# Power.net
KiCad netlist of a schematic drawn in Altium Designer
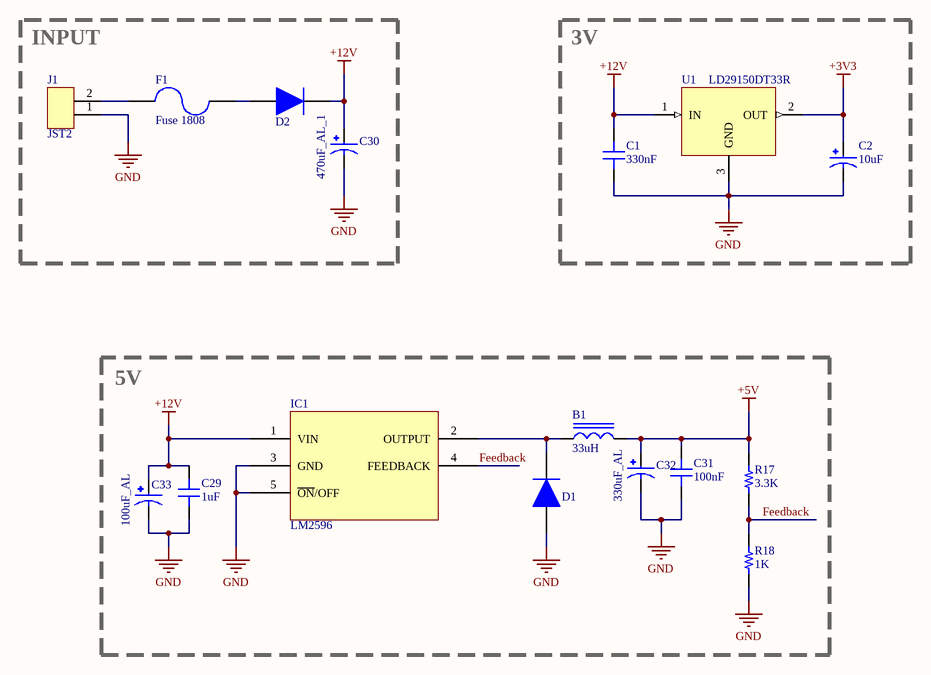
[diagram p0: Power.SchDoc]

(export (version "E")
  (design (tool "Eeschema 10.0.6"))
  (components
    (comp (ref "B1")
      (value "33uH")
      (footprint "DR125")
      (description "DR125")
      (libsource (lib "hava_kalitesi_olcumu") (part "33uH"))
    )
    (comp (ref "C1")
      (value "330nF")
      (footprint "CAP 0603_1608")
      (description "CERAMİC 1206 SMD")
      (libsource (lib "hava_kalitesi_olcumu") (part "330nF"))
    )
    (comp (ref "C2")
      (value "10uF")
      (footprint "TANTAL B-CASE")
      (description "TANTAL")
      (libsource (lib "hava_kalitesi_olcumu") (part "10uF"))
    )
    (comp (ref "C29")
      (value "1uF")
      (footprint "CAP 0603_1608")
      (description "CERAMİC 1206 SMD")
      (libsource (lib "hava_kalitesi_olcumu") (part "1uF"))
    )
    (comp (ref "C30")
      (value "470uF_AL_1")
      (footprint "10x12 Al Cap")
      (description "Aluminium Electrolytic Capacitors")
      (libsource (lib "hava_kalitesi_olcumu") (part "470uF_AL_1"))
    )
    (comp (ref "C31")
      (value "100nF")
      (footprint "CAP 0603_1608")
      (description "CERAMİC 1206 SMD")
      (libsource (lib "hava_kalitesi_olcumu") (part "100nF"))
    )
    (comp (ref "C32")
      (value "330uF_AL")
      (footprint "10x12 Al Cap")
      (description "Aluminium Electrolytic Capacitors")
      (libsource (lib "hava_kalitesi_olcumu") (part "330uF_AL"))
    )
    (comp (ref "C33")
      (value "100uF_AL")
      (footprint "10x12 Al Cap")
      (description "Aluminium Electrolytic Capacitors")
      (libsource (lib "hava_kalitesi_olcumu") (part "100uF_AL"))
    )
    (comp (ref "D1")
      (value "1N4148WS")
      (footprint "SOD323F")
      (description "Diode, Single, 75 V, 150 mA, 1 V, 4 ns")
      (fields (field (name "MANUFACTURER") "ON Semiconductor / Fairchild"))
      (libsource (lib "hava_kalitesi_olcumu") (part "1N4148WS"))
    )
    (comp (ref "D2")
      (value "1N4148WS")
      (footprint "SOD323F")
      (description "Diode, Single, 75 V, 150 mA, 1 V, 4 ns")
      (fields (field (name "MANUFACTURER") "ON Semiconductor / Fairchild"))
      (libsource (lib "hava_kalitesi_olcumu") (part "1N4148WS"))
    )
    (comp (ref "F1")
      (value "Fuse 1808")
      (footprint "1808")
      (description "FUSE BRD MNT 125VAC/VDC")
      (libsource (lib "hava_kalitesi_olcumu") (part "FUSE"))
    )
    (comp (ref "IC1")
      (value "LM2596")
      (footprint "D2PAK")
      (description "Buck Converter")
      (libsource (lib "hava_kalitesi_olcumu") (part "LM2596"))
    )
    (comp (ref "J1")
      (value "JST2")
      (footprint "JST2")
      (description "2 PIN 2.54MM")
      (libsource (lib "hava_kalitesi_olcumu") (part "JST2"))
    )
    (comp (ref "R17")
      (value "3.3K")
      (footprint "RES 0603_1608")
      (description "SMT RES 1206")
      (libsource (lib "hava_kalitesi_olcumu") (part "3.3K"))
    )
    (comp (ref "R18")
      (value "1K")
      (footprint "RES 0603_1608")
      (description "SMT RES 1206")
      (libsource (lib "hava_kalitesi_olcumu") (part "1K"))
    )
    (comp (ref "U1")
      (value "LD29150DT33R")
      (footprint "TO252-3 DPAK")
      (description "IC-29150 REG LDO 3V3 1.5A DPAK")
      (libsource (lib "hava_kalitesi_olcumu") (part "LD29150"))
    )
  )
  (nets
    (net (code "1") (name "+3V3") (class "Default")
      (node (ref "C2") (pin "+") (pinfunction "+_+") (pintype "passive"))
      (node (ref "U1") (pin "2") (pinfunction "OUT_2") (pintype "output"))
    )
    (net (code "2") (name "+5V") (class "Default")
      (node (ref "B1") (pin "2") (pinfunction "2_2") (pintype "passive"))
      (node (ref "C31") (pin "2") (pinfunction "2_2") (pintype "passive"))
      (node (ref "C32") (pin "1") (pinfunction "+_1") (pintype "passive"))
      (node (ref "R17") (pin "2") (pinfunction "2_2") (pintype "passive"))
    )
    (net (code "3") (name "+12V") (class "Default")
      (node (ref "C1") (pin "2") (pinfunction "2_2") (pintype "passive"))
      (node (ref "C29") (pin "2") (pinfunction "2_2") (pintype "passive"))
      (node (ref "C30") (pin "1") (pinfunction "+_1") (pintype "passive"))
      (node (ref "C33") (pin "1") (pinfunction "+_1") (pintype "passive"))
      (node (ref "D2") (pin "1") (pinfunction "1_1") (pintype "power_in"))
      (node (ref "IC1") (pin "1") (pinfunction "VIN_1") (pintype "passive"))
      (node (ref "U1") (pin "1") (pinfunction "IN_1") (pintype "input"))
    )
    (net (code "4") (name "/Feedback") (class "Default")
      (node (ref "IC1") (pin "4") (pinfunction "FEEDBACK_4") (pintype "passive"))
      (node (ref "R17") (pin "1") (pinfunction "1_1") (pintype "passive"))
      (node (ref "R18") (pin "2") (pinfunction "2_2") (pintype "passive"))
    )
    (net (code "5") (name "GND") (class "Default")
      (node (ref "C1") (pin "1") (pinfunction "1_1") (pintype "passive"))
      (node (ref "C2") (pin "-") (pinfunction "-_-") (pintype "passive"))
      (node (ref "C29") (pin "1") (pinfunction "1_1") (pintype "passive"))
      (node (ref "C30") (pin "2") (pinfunction "-_2") (pintype "passive"))
      (node (ref "C31") (pin "1") (pinfunction "1_1") (pintype "passive"))
      (node (ref "C32") (pin "2") (pinfunction "-_2") (pintype "passive"))
      (node (ref "C33") (pin "2") (pinfunction "-_2") (pintype "passive"))
      (node (ref "D1") (pin "2") (pinfunction "2_2") (pintype "power_in"))
      (node (ref "IC1") (pin "3") (pinfunction "GND_3") (pintype "passive"))
      (node (ref "IC1") (pin "5") (pinfunction "~{ON}/OFF_5") (pintype "passive"))
      (node (ref "J1") (pin "1") (pintype "passive"))
      (node (ref "R18") (pin "1") (pinfunction "1_1") (pintype "passive"))
      (node (ref "U1") (pin "3") (pinfunction "GND_3") (pintype "passive"))
    )
    (net (code "6") (name "Net-(D2-Pad2)") (class "Default")
      (node (ref "D2") (pin "2") (pinfunction "2_2") (pintype "power_in"))
      (node (ref "F1") (pin "2") (pinfunction "2_2") (pintype "passive"))
    )
    (net (code "7") (name "Net-(F1-Pad1)") (class "Default")
      (node (ref "F1") (pin "1") (pinfunction "1_1") (pintype "passive"))
      (node (ref "J1") (pin "2") (pintype "passive"))
    )
    (net (code "8") (name "Net-(IC1-OUTPUT)") (class "Default")
      (node (ref "B1") (pin "1") (pinfunction "1_1") (pintype "passive"))
      (node (ref "D1") (pin "1") (pinfunction "1_1") (pintype "power_in"))
      (node (ref "IC1") (pin "2") (pinfunction "OUTPUT_2") (pintype "passive"))
    )
  )
)
